# Freezer_Proto2.net
KiCad netlist of a schematic drawn in EAGLE
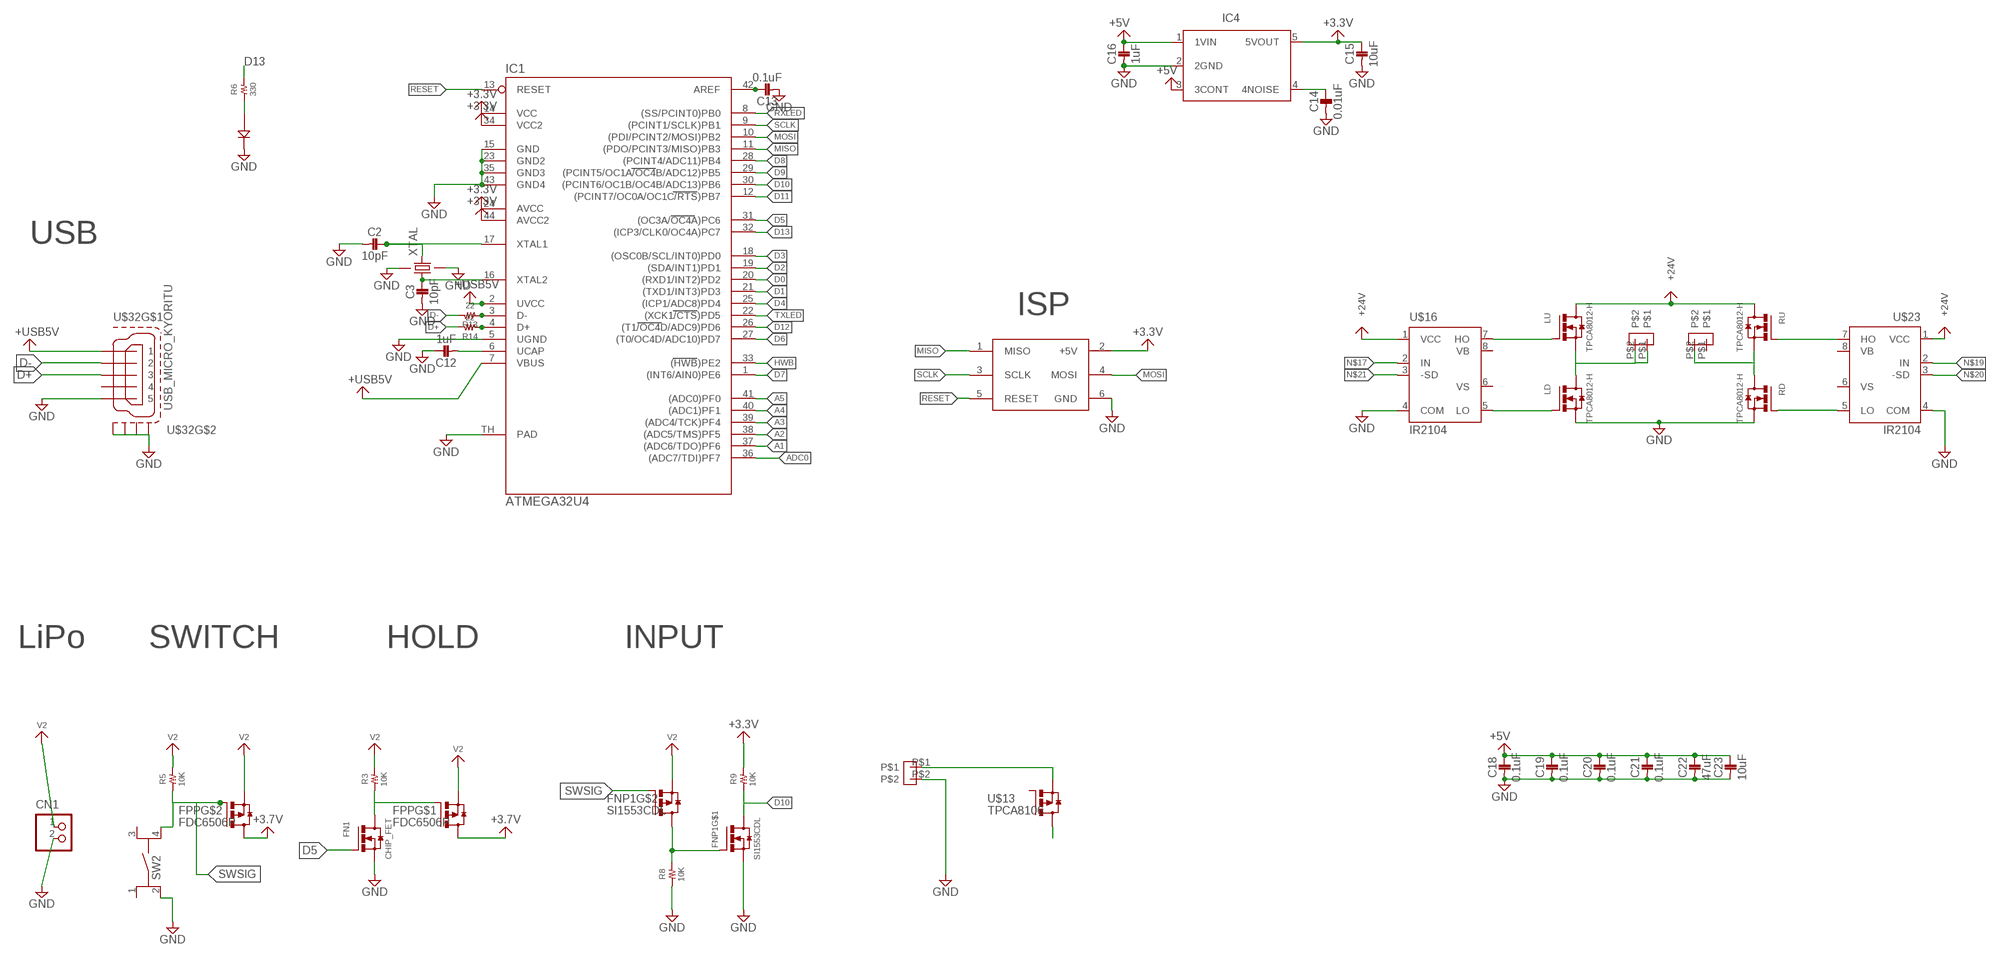
[diagram p0: schematic, sheet 1]

(export (version "E")
  (design (tool "Eeschema 10.0.6"))
  (components
    (comp (ref "C2")
      (value "10pF")
      (footprint "eagle-import:1005")
      (libsource (lib "eagle-import") (part "1005"))
    )
    (comp (ref "C3")
      (value "10pF")
      (footprint "eagle-import:1005")
      (libsource (lib "eagle-import") (part "1005"))
    )
    (comp (ref "C12")
      (value "1uF")
      (footprint "eagle-import:1005")
      (libsource (lib "eagle-import") (part "1005"))
    )
    (comp (ref "C13")
      (value "0.1uF")
      (footprint "eagle-import:1005")
      (libsource (lib "eagle-import") (part "1005"))
    )
    (comp (ref "C14")
      (value "0.01uF")
      (footprint "eagle-import:1608")
      (libsource (lib "eagle-import") (part "1608"))
    )
    (comp (ref "C15")
      (value "10uF")
      (footprint "eagle-import:1608")
      (libsource (lib "eagle-import") (part "1608"))
    )
    (comp (ref "C16")
      (value "1uF")
      (footprint "eagle-import:1005")
      (libsource (lib "eagle-import") (part "1005"))
    )
    (comp (ref "C18")
      (value "0.1uF")
      (footprint "eagle-import:1005")
      (libsource (lib "eagle-import") (part "1005"))
    )
    (comp (ref "C19")
      (value "0.1uF")
      (footprint "eagle-import:1005")
      (libsource (lib "eagle-import") (part "1005"))
    )
    (comp (ref "C20")
      (value "0.1uF")
      (footprint "eagle-import:1005")
      (libsource (lib "eagle-import") (part "1005"))
    )
    (comp (ref "C21")
      (value "0.1uF")
      (footprint "eagle-import:1005")
      (libsource (lib "eagle-import") (part "1005"))
    )
    (comp (ref "C22")
      (value "47uF")
      (footprint "eagle-import:1608")
      (libsource (lib "eagle-import") (part "1608"))
    )
    (comp (ref "C23")
      (value "10uF")
      (footprint "eagle-import:1608")
      (libsource (lib "eagle-import") (part "1608"))
    )
    (comp (ref "CN1")
      (value "S2B-PH-K-S")
      (footprint "eagle-import:S2B-PH-K-S")
      (libsource (lib "eagle-import") (part "S2B-PH-K-S"))
    )
    (comp (ref "FN1")
      (value "CHIP_FET")
      (footprint "eagle-import:SOT23")
      (libsource (lib "eagle-import") (part "CHIP_FET"))
    )
    (comp (ref "FNP1")
      (value "SI1553CDL")
      (footprint "eagle-import:SOT363")
      (libsource (lib "eagle-import") (part "SI1553CDL"))
    )
    (comp (ref "FPP")
      (value "FDC6506P")
      (footprint "eagle-import:SOT23-6")
      (libsource (lib "eagle-import") (part "FDC6506P"))
    )
    (comp (ref "IC1")
      (value "ATMEGA32U4")
      (footprint "eagle-import:QFN-44-7X7")
      (libsource (lib "eagle-import") (part "ATMEGA32U4"))
    )
    (comp (ref "IC4")
      (value "TAR5SB")
      (footprint "eagle-import:SSOP5-P-0.95")
      (libsource (lib "eagle-import") (part "TAR5SB"))
    )
    (comp (ref "LD")
      (value "TPCA8012-H")
      (footprint "eagle-import:2-5Q1A")
      (libsource (lib "eagle-import") (part "TPCA8012-H"))
    )
    (comp (ref "LED1")
      (value "1608")
      (footprint "eagle-import:1608")
      (libsource (lib "eagle-import") (part "10_LED_1608"))
    )
    (comp (ref "LU")
      (value "TPCA8012-H")
      (footprint "eagle-import:2-5Q1A")
      (libsource (lib "eagle-import") (part "TPCA8012-H"))
    )
    (comp (ref "R3")
      (value "10K")
      (footprint "eagle-import:1005")
      (libsource (lib "eagle-import") (part "RESISTOR_1005"))
    )
    (comp (ref "R5")
      (value "10K")
      (footprint "eagle-import:1005")
      (libsource (lib "eagle-import") (part "RESISTOR_1005"))
    )
    (comp (ref "R6")
      (value "330")
      (footprint "eagle-import:1005")
      (libsource (lib "eagle-import") (part "RESISTOR_1005"))
    )
    (comp (ref "R8")
      (value "10K")
      (footprint "eagle-import:1005")
      (libsource (lib "eagle-import") (part "RESISTOR_1005"))
    )
    (comp (ref "R9")
      (value "10K")
      (footprint "eagle-import:1005")
      (libsource (lib "eagle-import") (part "RESISTOR_1005"))
    )
    (comp (ref "R13")
      (value "22")
      (footprint "eagle-import:1005")
      (libsource (lib "eagle-import") (part "RESISTOR_1005"))
    )
    (comp (ref "R14")
      (value "22")
      (footprint "eagle-import:1005")
      (libsource (lib "eagle-import") (part "RESISTOR_1005"))
    )
    (comp (ref "RD")
      (value "TPCA8012-H")
      (footprint "eagle-import:2-5Q1A")
      (libsource (lib "eagle-import") (part "TPCA8012-H"))
    )
    (comp (ref "RU")
      (value "TPCA8012-H")
      (footprint "eagle-import:2-5Q1A")
      (libsource (lib "eagle-import") (part "TPCA8012-H"))
    )
    (comp (ref "SW2")
      (value "SKRPACE010")
      (footprint "eagle-import:SKRP")
      (libsource (lib "eagle-import") (part "SKRPACE010"))
    )
    (comp (ref "U$3")
      (value "ICSP")
      (footprint "eagle-import:ICSP")
      (libsource (lib "eagle-import") (part "ICSP"))
    )
    (comp (ref "U$7")
      (value "TERMINAL_2P")
      (footprint "eagle-import:TERMINAL_2P")
      (libsource (lib "eagle-import") (part "TERMINAL_2P"))
    )
    (comp (ref "U$13")
      (value "TPCA8106")
      (footprint "eagle-import:2-5Q1A")
      (libsource (lib "eagle-import") (part "TPCA8106"))
    )
    (comp (ref "U$16")
      (value "IR2104")
      (footprint "eagle-import:SOIC8")
      (libsource (lib "eagle-import") (part "IR2104"))
    )
    (comp (ref "U$23")
      (value "IR2104")
      (footprint "eagle-import:SOIC8")
      (libsource (lib "eagle-import") (part "IR2104"))
    )
    (comp (ref "U$32")
      (value "USB_MICRO_KYORITU")
      (footprint "eagle-import:USB_MICRO_KYORITU")
      (libsource (lib "eagle-import") (part "USB_MICRO_KYORITU"))
    )
    (comp (ref "U$38")
      (value "TERMINAL_2P")
      (footprint "eagle-import:TERMINAL_2P")
      (libsource (lib "eagle-import") (part "TERMINAL_2P"))
    )
    (comp (ref "U$43")
      (value "TERMINAL_2P")
      (footprint "eagle-import:TERMINAL_2P")
      (libsource (lib "eagle-import") (part "TERMINAL_2P"))
    )
    (comp (ref "XTAL")
      (value "FA-238")
      (footprint "eagle-import:FA-238")
      (libsource (lib "eagle-import") (part "FA-238"))
    )
  )
  (nets
    (net (code "1") (name "+3.3V") (class "Default")
      (node (ref "C15") (pin "P$1") (pinfunction "1_P$1") (pintype "passive"))
      (node (ref "IC1") (pin "14") (pinfunction "VCC_14") (pintype "bidirectional"))
      (node (ref "IC1") (pin "24") (pinfunction "AVCC_24") (pintype "bidirectional"))
      (node (ref "IC1") (pin "34") (pinfunction "VCC2_34") (pintype "bidirectional"))
      (node (ref "IC1") (pin "44") (pinfunction "AVCC2_44") (pintype "bidirectional"))
      (node (ref "IC4") (pin "5") (pinfunction "5VOUT_5") (pintype "bidirectional"))
      (node (ref "R9") (pin "2") (pinfunction "P$2_2") (pintype "passive"))
      (node (ref "U$3") (pin "2") (pinfunction "+5V_2") (pintype "bidirectional"))
    )
    (net (code "2") (name "+3.7V") (class "Default")
      (node (ref "FPP") (pin "4") (pinfunction "D_4") (pintype "passive"))
      (node (ref "FPP") (pin "6") (pinfunction "D_6") (pintype "passive"))
    )
    (net (code "3") (name "+5V") (class "Default")
      (node (ref "C16") (pin "1") (pinfunction "1_1") (pintype "passive"))
      (node (ref "C18") (pin "1") (pinfunction "1_1") (pintype "passive"))
      (node (ref "C19") (pin "1") (pinfunction "1_1") (pintype "passive"))
      (node (ref "C20") (pin "1") (pinfunction "1_1") (pintype "passive"))
      (node (ref "C21") (pin "1") (pinfunction "1_1") (pintype "passive"))
      (node (ref "C22") (pin "P$1") (pinfunction "1_P$1") (pintype "passive"))
      (node (ref "C23") (pin "P$1") (pinfunction "1_P$1") (pintype "passive"))
      (node (ref "IC4") (pin "1") (pinfunction "1VIN_1") (pintype "bidirectional"))
      (node (ref "IC4") (pin "3") (pinfunction "3CONT_3") (pintype "bidirectional"))
    )
    (net (code "4") (name "+24V") (class "Default")
      (node (ref "LU") (pin "5") (pinfunction "D_5") (pintype "passive"))
      (node (ref "LU") (pin "6") (pinfunction "D_6") (pintype "passive"))
      (node (ref "LU") (pin "7") (pinfunction "D_7") (pintype "passive"))
      (node (ref "LU") (pin "8") (pinfunction "D_8") (pintype "passive"))
      (node (ref "RU") (pin "5") (pinfunction "D_5") (pintype "passive"))
      (node (ref "RU") (pin "6") (pinfunction "D_6") (pintype "passive"))
      (node (ref "RU") (pin "7") (pinfunction "D_7") (pintype "passive"))
      (node (ref "RU") (pin "8") (pinfunction "D_8") (pintype "passive"))
      (node (ref "U$16") (pin "1") (pinfunction "VCC_1") (pintype "power_in"))
      (node (ref "U$23") (pin "1") (pinfunction "VCC_1") (pintype "power_in"))
    )
    (net (code "5") (name "+USB5V") (class "Default")
      (node (ref "IC1") (pin "2") (pinfunction "UVCC_2") (pintype "bidirectional"))
      (node (ref "IC1") (pin "7") (pinfunction "VBUS_7") (pintype "bidirectional"))
      (node (ref "U$32") (pin "1") (pinfunction "1_1") (pintype "input"))
    )
    (net (code "6") (name "A1") (class "Default")
      (node (ref "IC1") (pin "37") (pinfunction "(ADC6/TDO)PF6_37") (pintype "bidirectional"))
    )
    (net (code "7") (name "A2") (class "Default")
      (node (ref "IC1") (pin "38") (pinfunction "(ADC5/TMS)PF5_38") (pintype "bidirectional"))
    )
    (net (code "8") (name "A3") (class "Default")
      (node (ref "IC1") (pin "39") (pinfunction "(ADC4/TCK)PF4_39") (pintype "bidirectional"))
    )
    (net (code "9") (name "A4") (class "Default")
      (node (ref "IC1") (pin "40") (pinfunction "(ADC1)PF1_40") (pintype "bidirectional"))
    )
    (net (code "10") (name "A5") (class "Default")
      (node (ref "IC1") (pin "41") (pinfunction "(ADC0)PF0_41") (pintype "bidirectional"))
    )
    (net (code "11") (name "ADC0") (class "Default")
      (node (ref "IC1") (pin "36") (pinfunction "(ADC7/TDI)PF7_36") (pintype "bidirectional"))
    )
    (net (code "12") (name "D+") (class "Default")
      (node (ref "R14") (pin "2") (pinfunction "P$2_2") (pintype "passive"))
      (node (ref "U$32") (pin "3") (pinfunction "3_3") (pintype "input"))
    )
    (net (code "13") (name "D-") (class "Default")
      (node (ref "R13") (pin "2") (pinfunction "P$2_2") (pintype "passive"))
      (node (ref "U$32") (pin "2") (pinfunction "2_2") (pintype "input"))
    )
    (net (code "14") (name "D0") (class "Default")
      (node (ref "IC1") (pin "20") (pinfunction "(RXD1/INT2)PD2_20") (pintype "bidirectional"))
    )
    (net (code "15") (name "D1") (class "Default")
      (node (ref "IC1") (pin "21") (pinfunction "(TXD1/INT3)PD3_21") (pintype "bidirectional"))
    )
    (net (code "16") (name "D2") (class "Default")
      (node (ref "IC1") (pin "19") (pinfunction "(SDA/INT1)PD1_19") (pintype "bidirectional"))
    )
    (net (code "17") (name "D3") (class "Default")
      (node (ref "IC1") (pin "18") (pinfunction "(OSC0B/SCL/INT0)PD0_18") (pintype "bidirectional"))
    )
    (net (code "18") (name "D4") (class "Default")
      (node (ref "IC1") (pin "25") (pinfunction "(ICP1/ADC8)PD4_25") (pintype "bidirectional"))
    )
    (net (code "19") (name "D5") (class "Default")
      (node (ref "FN1") (pin "1") (pinfunction "G_1") (pintype "passive"))
      (node (ref "IC1") (pin "31") (pinfunction "(OC3A/OC4A)PC6_31") (pintype "bidirectional"))
    )
    (net (code "20") (name "D6") (class "Default")
      (node (ref "IC1") (pin "27") (pinfunction "(T0/OC4D/ADC10)PD7_27") (pintype "bidirectional"))
    )
    (net (code "21") (name "D7") (class "Default")
      (node (ref "IC1") (pin "1") (pinfunction "(INT6/AIN0)PE6_1") (pintype "bidirectional"))
    )
    (net (code "22") (name "D8") (class "Default")
      (node (ref "IC1") (pin "28") (pinfunction "(PCINT4/ADC11)PB4_28") (pintype "bidirectional"))
    )
    (net (code "23") (name "D9") (class "Default")
      (node (ref "IC1") (pin "29") (pinfunction "(PCINT5/OC1A/OC4B/ADC12)PB5_29") (pintype "bidirectional"))
    )
    (net (code "24") (name "D10") (class "Default")
      (node (ref "FNP1") (pin "6") (pinfunction "D_6") (pintype "passive"))
      (node (ref "IC1") (pin "30") (pinfunction "(PCINT6/OC1B/OC4B/ADC13)PB6_30") (pintype "bidirectional"))
      (node (ref "R9") (pin "1") (pinfunction "P$1_1") (pintype "passive"))
    )
    (net (code "25") (name "D11") (class "Default")
      (node (ref "IC1") (pin "12") (pinfunction "(PCINT7/OC0A/OC1C/RTS)PB7_12") (pintype "bidirectional"))
    )
    (net (code "26") (name "D12") (class "Default")
      (node (ref "IC1") (pin "26") (pinfunction "(T1/OC4D/ADC9)PD6_26") (pintype "bidirectional"))
    )
    (net (code "27") (name "D13") (class "Default")
      (node (ref "IC1") (pin "32") (pinfunction "(ICP3/CLK0/OC4A)PC7_32") (pintype "bidirectional"))
      (node (ref "R6") (pin "2") (pinfunction "P$2_2") (pintype "passive"))
    )
    (net (code "28") (name "GND") (class "Default")
      (node (ref "C12") (pin "1") (pinfunction "1_1") (pintype "passive"))
      (node (ref "C13") (pin "2") (pinfunction "2_2") (pintype "passive"))
      (node (ref "C14") (pin "P$2") (pinfunction "2_P$2") (pintype "passive"))
      (node (ref "C15") (pin "P$2") (pinfunction "2_P$2") (pintype "passive"))
      (node (ref "C16") (pin "2") (pinfunction "2_2") (pintype "passive"))
      (node (ref "C18") (pin "2") (pinfunction "2_2") (pintype "passive"))
      (node (ref "C19") (pin "2") (pinfunction "2_2") (pintype "passive"))
      (node (ref "C2") (pin "2") (pinfunction "2_2") (pintype "passive"))
      (node (ref "C20") (pin "2") (pinfunction "2_2") (pintype "passive"))
      (node (ref "C21") (pin "2") (pinfunction "2_2") (pintype "passive"))
      (node (ref "C22") (pin "P$2") (pinfunction "2_P$2") (pintype "passive"))
      (node (ref "C23") (pin "P$2") (pinfunction "2_P$2") (pintype "passive"))
      (node (ref "C3") (pin "2") (pinfunction "2_2") (pintype "passive"))
      (node (ref "CN1") (pin "2") (pinfunction "2_2") (pintype "passive"))
      (node (ref "FN1") (pin "2") (pinfunction "S_2") (pintype "passive"))
      (node (ref "FNP1") (pin "1") (pinfunction "S_1") (pintype "passive"))
      (node (ref "IC1") (pin "15") (pinfunction "GND_15") (pintype "bidirectional"))
      (node (ref "IC1") (pin "23") (pinfunction "GND2_23") (pintype "bidirectional"))
      (node (ref "IC1") (pin "35") (pinfunction "GND3_35") (pintype "bidirectional"))
      (node (ref "IC1") (pin "43") (pinfunction "GND4_43") (pintype "bidirectional"))
      (node (ref "IC1") (pin "5") (pinfunction "UGND_5") (pintype "bidirectional"))
      (node (ref "IC1") (pin "TH") (pinfunction "PAD_TH") (pintype "bidirectional"))
      (node (ref "IC4") (pin "2") (pinfunction "2GND_2") (pintype "bidirectional"))
      (node (ref "LD") (pin "1") (pinfunction "S_1") (pintype "passive"))
      (node (ref "LD") (pin "2") (pinfunction "S_2") (pintype "passive"))
      (node (ref "LD") (pin "3") (pinfunction "S_3") (pintype "passive"))
      (node (ref "LED1") (pin "2") (pinfunction "K_2") (pintype "bidirectional"))
      (node (ref "R8") (pin "1") (pinfunction "P$1_1") (pintype "passive"))
      (node (ref "RD") (pin "1") (pinfunction "S_1") (pintype "passive"))
      (node (ref "RD") (pin "2") (pinfunction "S_2") (pintype "passive"))
      (node (ref "RD") (pin "3") (pinfunction "S_3") (pintype "passive"))
      (node (ref "SW2") (pin "2") (pinfunction "1__2") (pintype "passive"))
      (node (ref "U$16") (pin "4") (pinfunction "COM_4") (pintype "power_in"))
      (node (ref "U$23") (pin "4") (pinfunction "COM_4") (pintype "power_in"))
      (node (ref "U$3") (pin "6") (pinfunction "GND_6") (pintype "bidirectional"))
      (node (ref "U$32") (pin "5") (pinfunction "5_5") (pintype "input"))
      (node (ref "U$32") (pin "M1") (pinfunction "S1_M1") (pintype "passive"))
      (node (ref "U$32") (pin "M2") (pinfunction "S2_M2") (pintype "passive"))
      (node (ref "U$32") (pin "M3") (pinfunction "S3_M3") (pintype "passive"))
      (node (ref "U$32") (pin "M4") (pinfunction "S4_M4") (pintype "passive"))
      (node (ref "U$7") (pin "P$2") (pinfunction "P$2_P$2") (pintype "bidirectional"))
      (node (ref "XTAL") (pin "2") (pinfunction "2_2") (pintype "bidirectional"))
      (node (ref "XTAL") (pin "4") (pinfunction "4_4") (pintype "bidirectional"))
    )
    (net (code "29") (name "HWB") (class "Default")
      (node (ref "IC1") (pin "33") (pinfunction "(HWB)PE2_33") (pintype "bidirectional"))
    )
    (net (code "30") (name "MISO") (class "Default")
      (node (ref "IC1") (pin "11") (pinfunction "(PDO/PCINT3/MISO)PB3_11") (pintype "bidirectional"))
      (node (ref "U$3") (pin "1") (pinfunction "MISO_1") (pintype "bidirectional"))
    )
    (net (code "31") (name "MOSI") (class "Default")
      (node (ref "IC1") (pin "10") (pinfunction "(PDI/PCINT2/MOSI)PB2_10") (pintype "bidirectional"))
      (node (ref "U$3") (pin "4") (pinfunction "MOSI_4") (pintype "bidirectional"))
    )
    (net (code "32") (name "N$17") (class "Default")
      (node (ref "U$16") (pin "2") (pinfunction "IN_2") (pintype "input"))
    )
    (net (code "33") (name "N$19") (class "Default")
      (node (ref "U$23") (pin "2") (pinfunction "IN_2") (pintype "input"))
    )
    (net (code "34") (name "N$20") (class "Default")
      (node (ref "U$23") (pin "3") (pinfunction "-SD_3") (pintype "input"))
    )
    (net (code "35") (name "N$21") (class "Default")
      (node (ref "U$16") (pin "3") (pinfunction "-SD_3") (pintype "input"))
    )
    (net (code "36") (name "Net-(C14-1)") (class "Default")
      (node (ref "C14") (pin "P$1") (pinfunction "1_P$1") (pintype "passive"))
      (node (ref "IC4") (pin "4") (pinfunction "4NOISE_4") (pintype "bidirectional"))
    )
    (net (code "37") (name "Net-(FN1-D)") (class "Default")
      (node (ref "FN1") (pin "3") (pinfunction "D_3") (pintype "passive"))
      (node (ref "FPP") (pin "1") (pinfunction "G_1") (pintype "passive"))
      (node (ref "R3") (pin "1") (pinfunction "P$1_1") (pintype "passive"))
    )
    (net (code "38") (name "Net-(FNP1A-G)") (class "Default")
      (node (ref "FNP1") (pin "2") (pinfunction "G_2") (pintype "passive"))
      (node (ref "FNP1") (pin "3") (pinfunction "D_3") (pintype "passive"))
      (node (ref "R8") (pin "2") (pinfunction "P$2_2") (pintype "passive"))
    )
    (net (code "39") (name "Net-(IC1-AREF)") (class "Default")
      (node (ref "C13") (pin "1") (pinfunction "1_1") (pintype "passive"))
      (node (ref "IC1") (pin "42") (pinfunction "AREF_42") (pintype "bidirectional"))
    )
    (net (code "40") (name "Net-(IC1-D+)") (class "Default")
      (node (ref "IC1") (pin "4") (pinfunction "D+_4") (pintype "bidirectional"))
      (node (ref "R14") (pin "1") (pinfunction "P$1_1") (pintype "passive"))
    )
    (net (code "41") (name "Net-(IC1-D-)") (class "Default")
      (node (ref "IC1") (pin "3") (pinfunction "D-_3") (pintype "bidirectional"))
      (node (ref "R13") (pin "1") (pinfunction "P$1_1") (pintype "passive"))
    )
    (net (code "42") (name "Net-(IC1-UCAP)") (class "Default")
      (node (ref "C12") (pin "2") (pinfunction "2_2") (pintype "passive"))
      (node (ref "IC1") (pin "6") (pinfunction "UCAP_6") (pintype "bidirectional"))
    )
    (net (code "43") (name "Net-(IC1-XTAL1)") (class "Default")
      (node (ref "C2") (pin "1") (pinfunction "1_1") (pintype "passive"))
      (node (ref "IC1") (pin "17") (pinfunction "XTAL1_17") (pintype "bidirectional"))
      (node (ref "XTAL") (pin "3") (pinfunction "3_3") (pintype "passive"))
    )
    (net (code "44") (name "Net-(IC1-XTAL2)") (class "Default")
      (node (ref "C3") (pin "1") (pinfunction "1_1") (pintype "passive"))
      (node (ref "IC1") (pin "16") (pinfunction "XTAL2_16") (pintype "bidirectional"))
      (node (ref "XTAL") (pin "1") (pinfunction "1_1") (pintype "passive"))
    )
    (net (code "45") (name "Net-(LD-D-Pad5)") (class "Default")
      (node (ref "LD") (pin "5") (pinfunction "D_5") (pintype "passive"))
      (node (ref "LD") (pin "6") (pinfunction "D_6") (pintype "passive"))
      (node (ref "LD") (pin "7") (pinfunction "D_7") (pintype "passive"))
      (node (ref "LD") (pin "8") (pinfunction "D_8") (pintype "passive"))
      (node (ref "LU") (pin "1") (pinfunction "S_1") (pintype "passive"))
      (node (ref "LU") (pin "2") (pinfunction "S_2") (pintype "passive"))
      (node (ref "LU") (pin "3") (pinfunction "S_3") (pintype "passive"))
      (node (ref "U$38") (pin "P$1") (pinfunction "P$1_P$1") (pintype "bidirectional"))
      (node (ref "U$38") (pin "P$2") (pinfunction "P$2_P$2") (pintype "bidirectional"))
    )
    (net (code "46") (name "Net-(LD-G)") (class "Default")
      (node (ref "LD") (pin "4") (pinfunction "G_4") (pintype "passive"))
      (node (ref "U$16") (pin "5") (pinfunction "LO_5") (pintype "output"))
    )
    (net (code "47") (name "Net-(LED1-A)") (class "Default")
      (node (ref "LED1") (pin "1") (pinfunction "A_1") (pintype "bidirectional"))
      (node (ref "R6") (pin "1") (pinfunction "P$1_1") (pintype "passive"))
    )
    (net (code "48") (name "Net-(LU-G)") (class "Default")
      (node (ref "LU") (pin "4") (pinfunction "G_4") (pintype "passive"))
      (node (ref "U$16") (pin "7") (pinfunction "HO_7") (pintype "output"))
    )
    (net (code "49") (name "Net-(RD-D-Pad5)") (class "Default")
      (node (ref "RD") (pin "5") (pinfunction "D_5") (pintype "passive"))
      (node (ref "RD") (pin "6") (pinfunction "D_6") (pintype "passive"))
      (node (ref "RD") (pin "7") (pinfunction "D_7") (pintype "passive"))
      (node (ref "RD") (pin "8") (pinfunction "D_8") (pintype "passive"))
      (node (ref "RU") (pin "1") (pinfunction "S_1") (pintype "passive"))
      (node (ref "RU") (pin "2") (pinfunction "S_2") (pintype "passive"))
      (node (ref "RU") (pin "3") (pinfunction "S_3") (pintype "passive"))
      (node (ref "U$43") (pin "P$2") (pinfunction "P$2_P$2") (pintype "bidirectional"))
    )
    (net (code "50") (name "Net-(RD-G)") (class "Default")
      (node (ref "RD") (pin "4") (pinfunction "G_4") (pintype "passive"))
      (node (ref "U$23") (pin "5") (pinfunction "LO_5") (pintype "output"))
    )
    (net (code "51") (name "Net-(RU-G)") (class "Default")
      (node (ref "RU") (pin "4") (pinfunction "G_4") (pintype "passive"))
      (node (ref "U$23") (pin "7") (pinfunction "HO_7") (pintype "output"))
    )
    (net (code "52") (name "Net-(U$13-D-Pad5)") (class "Default")
      (node (ref "U$13") (pin "5") (pinfunction "D_5") (pintype "passive"))
      (node (ref "U$13") (pin "6") (pinfunction "D_6") (pintype "passive"))
      (node (ref "U$13") (pin "7") (pinfunction "D_7") (pintype "passive"))
      (node (ref "U$13") (pin "8") (pinfunction "D_8") (pintype "passive"))
    )
    (net (code "53") (name "Net-(U$13-S-Pad1)") (class "Default")
      (node (ref "U$13") (pin "1") (pinfunction "S_1") (pintype "passive"))
      (node (ref "U$13") (pin "2") (pinfunction "S_2") (pintype "passive"))
      (node (ref "U$13") (pin "3") (pinfunction "S_3") (pintype "passive"))
      (node (ref "U$7") (pin "P$1") (pinfunction "P$1_P$1") (pintype "bidirectional"))
    )
    (net (code "54") (name "RESET") (class "Default")
      (node (ref "IC1") (pin "13") (pinfunction "RESET_13") (pintype "bidirectional"))
      (node (ref "U$3") (pin "5") (pinfunction "RESET_5") (pintype "bidirectional"))
    )
    (net (code "55") (name "RXLED") (class "Default")
      (node (ref "IC1") (pin "8") (pinfunction "(SS/PCINT0)PB0_8") (pintype "bidirectional"))
    )
    (net (code "56") (name "SCLK") (class "Default")
      (node (ref "IC1") (pin "9") (pinfunction "(PCINT1/SCLK)PB1_9") (pintype "bidirectional"))
      (node (ref "U$3") (pin "3") (pinfunction "SCLK_3") (pintype "bidirectional"))
    )
    (net (code "57") (name "SWSIG") (class "Default")
      (node (ref "FNP1") (pin "5") (pinfunction "G_5") (pintype "passive"))
      (node (ref "FPP") (pin "3") (pinfunction "G_3") (pintype "passive"))
      (node (ref "R5") (pin "1") (pinfunction "P$1_1") (pintype "passive"))
      (node (ref "SW2") (pin "4") (pinfunction "2__4") (pintype "passive"))
    )
    (net (code "58") (name "TXLED") (class "Default")
      (node (ref "IC1") (pin "22") (pinfunction "(XCK1/CTS)PD5_22") (pintype "bidirectional"))
    )
    (net (code "59") (name "V2") (class "Default")
      (node (ref "CN1") (pin "1") (pinfunction "1_1") (pintype "passive"))
      (node (ref "FNP1") (pin "4") (pinfunction "S_4") (pintype "passive"))
      (node (ref "FPP") (pin "2") (pinfunction "S_2") (pintype "passive"))
      (node (ref "FPP") (pin "5") (pinfunction "S_5") (pintype "passive"))
      (node (ref "R3") (pin "2") (pinfunction "P$2_2") (pintype "passive"))
      (node (ref "R5") (pin "2") (pinfunction "P$2_2") (pintype "passive"))
    )
    (net (code "60") (name "unconnected-(SW2-2-Pad3)") (class "Default")
      (node (ref "SW2") (pin "3") (pinfunction "2_3") (pintype "passive"))
    )
    (net (code "61") (name "unconnected-(SW2-Pad1)") (class "Default")
      (node (ref "SW2") (pin "1") (pinfunction "1_1") (pintype "passive"))
    )
    (net (code "62") (name "unconnected-(U$13-G-Pad4)") (class "Default")
      (node (ref "U$13") (pin "4") (pinfunction "G_4") (pintype "passive"))
    )
    (net (code "63") (name "unconnected-(U$16-VB-Pad8)") (class "Default")
      (node (ref "U$16") (pin "8") (pinfunction "VB_8") (pintype "passive"))
    )
    (net (code "64") (name "unconnected-(U$16-VS-Pad6)") (class "Default")
      (node (ref "U$16") (pin "6") (pinfunction "VS_6") (pintype "input"))
    )
    (net (code "65") (name "unconnected-(U$23-VB-Pad8)") (class "Default")
      (node (ref "U$23") (pin "8") (pinfunction "VB_8") (pintype "passive"))
    )
    (net (code "66") (name "unconnected-(U$23-VS-Pad6)") (class "Default")
      (node (ref "U$23") (pin "6") (pinfunction "VS_6") (pintype "input"))
    )
    (net (code "67") (name "unconnected-(U$32-Pad4)") (class "Default")
      (node (ref "U$32") (pin "4") (pinfunction "4_4") (pintype "input"))
    )
    (net (code "68") (name "unconnected-(U$43-PadP$1)") (class "Default")
      (node (ref "U$43") (pin "P$1") (pinfunction "P$1_P$1") (pintype "bidirectional"))
    )
  )
)
